# XiBank_V1_0.net
KiCad netlist of a schematic drawn in Altium Designer
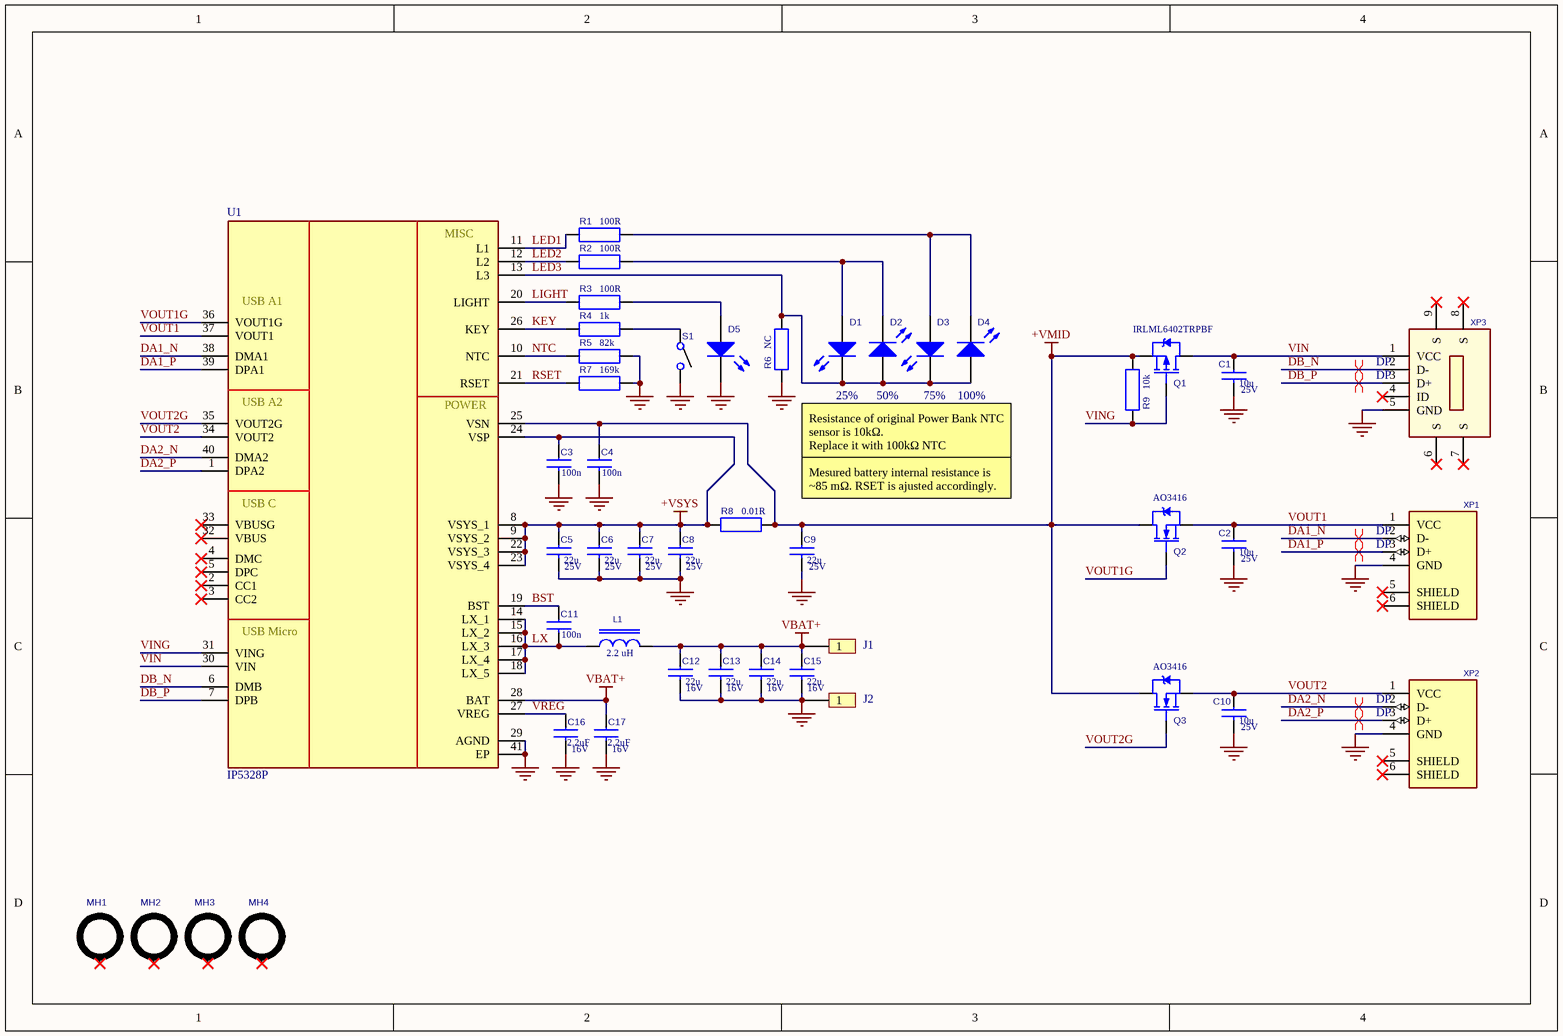
[diagram p0: XiBank_V1.0.SchDoc]

(export (version "E")
  (design (tool "Eeschema 10.0.6"))
  (components
    (comp (ref "C1")
      (value "10u")
      (footprint "CC0805")
      (description "10 µF ±10% 25V Ceramic Capacitor X5R 0805 (2012 Metric)")
      (fields
        (field (name "VOLTAGE") "25V")
        (field (name "TOLERANCE") "10%")
        (field (name "MANUFACTURER") "Samsung Electro-Mechanics")
      )
      (libsource (lib "Aldiva_Altium_Library") (part "Capacitor_nonpolar_case"))
    )
    (comp (ref "C2")
      (value "10u")
      (footprint "CC0805")
      (description "10 µF ±10% 25V Ceramic Capacitor X5R 0805 (2012 Metric)")
      (fields
        (field (name "VOLTAGE") "25V")
        (field (name "TOLERANCE") "10%")
        (field (name "MANUFACTURER") "Samsung Electro-Mechanics")
      )
      (libsource (lib "Aldiva_Altium_Library") (part "Capacitor_nonpolar_case"))
    )
    (comp (ref "C3")
      (value "100n")
      (footprint "CC0603")
      (description "0.1 µF ±10% 50V Ceramic Capacitor X7R 0603 (1608 Metric)")
      (fields (field (name "VOLTAGE") "50V") (field (name "TOLERANCE") "10%"))
      (libsource (lib "Aldiva_Altium_Library") (part "Capacitor_nonpolar_case"))
    )
    (comp (ref "C4")
      (value "100n")
      (footprint "CC0603")
      (description "0.1 µF ±10% 50V Ceramic Capacitor X7R 0603 (1608 Metric)")
      (fields (field (name "VOLTAGE") "50V") (field (name "TOLERANCE") "10%"))
      (libsource (lib "Aldiva_Altium_Library") (part "Capacitor_nonpolar_case"))
    )
    (comp (ref "C5")
      (value "22u")
      (footprint "CC0805")
      (description "22 µF ±20% 25V Ceramic Capacitor X5R 0805 (2012 Metric)")
      (fields
        (field (name "VOLTAGE") "25V")
        (field (name "TOLERANCE") "10%")
        (field (name "MANUFACTURER") "Samsung Electro-Mechanics")
      )
      (libsource (lib "Aldiva_Altium_Library") (part "Capacitor_nonpolar_case"))
    )
    (comp (ref "C6")
      (value "22u")
      (footprint "CC0805")
      (description "22 µF ±20% 25V Ceramic Capacitor X5R 0805 (2012 Metric)")
      (fields
        (field (name "VOLTAGE") "25V")
        (field (name "TOLERANCE") "10%")
        (field (name "MANUFACTURER") "Samsung Electro-Mechanics")
      )
      (libsource (lib "Aldiva_Altium_Library") (part "Capacitor_nonpolar_case"))
    )
    (comp (ref "C7")
      (value "22u")
      (footprint "CC0805")
      (description "22 µF ±20% 25V Ceramic Capacitor X5R 0805 (2012 Metric)")
      (fields
        (field (name "VOLTAGE") "25V")
        (field (name "TOLERANCE") "10%")
        (field (name "MANUFACTURER") "Samsung Electro-Mechanics")
      )
      (libsource (lib "Aldiva_Altium_Library") (part "Capacitor_nonpolar_case"))
    )
    (comp (ref "C8")
      (value "22u")
      (footprint "CC0805")
      (description "22 µF ±20% 25V Ceramic Capacitor X5R 0805 (2012 Metric)")
      (fields
        (field (name "VOLTAGE") "25V")
        (field (name "TOLERANCE") "10%")
        (field (name "MANUFACTURER") "Samsung Electro-Mechanics")
      )
      (libsource (lib "Aldiva_Altium_Library") (part "Capacitor_nonpolar_case"))
    )
    (comp (ref "C9")
      (value "22u")
      (footprint "CC0805")
      (description "22 µF ±20% 25V Ceramic Capacitor X5R 0805 (2012 Metric)")
      (fields
        (field (name "VOLTAGE") "25V")
        (field (name "TOLERANCE") "10%")
        (field (name "MANUFACTURER") "Samsung Electro-Mechanics")
      )
      (libsource (lib "Aldiva_Altium_Library") (part "Capacitor_nonpolar_case"))
    )
    (comp (ref "C10")
      (value "10u")
      (footprint "CC0805")
      (description "10 µF ±10% 25V Ceramic Capacitor X5R 0805 (2012 Metric)")
      (fields
        (field (name "VOLTAGE") "25V")
        (field (name "TOLERANCE") "10%")
        (field (name "MANUFACTURER") "Samsung Electro-Mechanics")
      )
      (libsource (lib "Aldiva_Altium_Library") (part "Capacitor_nonpolar_case"))
    )
    (comp (ref "C11")
      (value "100n")
      (footprint "CC0603")
      (description "0.1 µF ±10% 50V Ceramic Capacitor X7R 0603 (1608 Metric)")
      (fields (field (name "VOLTAGE") "50V") (field (name "TOLERANCE") "10%"))
      (libsource (lib "Aldiva_Altium_Library") (part "Capacitor_nonpolar_case"))
    )
    (comp (ref "C12")
      (value "22u")
      (footprint "CC0805")
      (description "22 µF ±20% 16V Ceramic Capacitor X5R 0805 (2012 Metric)")
      (fields
        (field (name "VOLTAGE") "16V")
        (field (name "TOLERANCE") "10%")
        (field (name "MANUFACTURER") "Samsung Electro-Mechanics")
      )
      (libsource (lib "Aldiva_Altium_Library") (part "Capacitor_nonpolar_case"))
    )
    (comp (ref "C13")
      (value "22u")
      (footprint "CC0805")
      (description "22 µF ±20% 16V Ceramic Capacitor X5R 0805 (2012 Metric)")
      (fields
        (field (name "VOLTAGE") "16V")
        (field (name "TOLERANCE") "10%")
        (field (name "MANUFACTURER") "Samsung Electro-Mechanics")
      )
      (libsource (lib "Aldiva_Altium_Library") (part "Capacitor_nonpolar_case"))
    )
    (comp (ref "C14")
      (value "22u")
      (footprint "CC0805")
      (description "22 µF ±20% 16V Ceramic Capacitor X5R 0805 (2012 Metric)")
      (fields
        (field (name "VOLTAGE") "16V")
        (field (name "TOLERANCE") "10%")
        (field (name "MANUFACTURER") "Samsung Electro-Mechanics")
      )
      (libsource (lib "Aldiva_Altium_Library") (part "Capacitor_nonpolar_case"))
    )
    (comp (ref "C15")
      (value "22u")
      (footprint "CC0805")
      (description "22 µF ±20% 16V Ceramic Capacitor X5R 0805 (2012 Metric)")
      (fields
        (field (name "VOLTAGE") "16V")
        (field (name "TOLERANCE") "10%")
        (field (name "MANUFACTURER") "Samsung Electro-Mechanics")
      )
      (libsource (lib "Aldiva_Altium_Library") (part "Capacitor_nonpolar_case"))
    )
    (comp (ref "C16")
      (value "2.2uF")
      (footprint "CC0603")
      (description "2.2 µF ±10% 16V Ceramic Capacitor X5R 0603 (1608 Metric)")
      (fields
        (field (name "VOLTAGE") "16V")
        (field (name "TOLERANCE") "10%")
        (field (name "MANUFACTURER") "Samsung Electro-Mechanics")
      )
      (libsource (lib "Aldiva_Altium_Library") (part "Capacitor_nonpolar_case"))
    )
    (comp (ref "C17")
      (value "2.2uF")
      (footprint "CC0603")
      (description "2.2 µF ±10% 16V Ceramic Capacitor X5R 0603 (1608 Metric)")
      (fields
        (field (name "VOLTAGE") "16V")
        (field (name "TOLERANCE") "10%")
        (field (name "MANUFACTURER") "Samsung Electro-Mechanics")
      )
      (libsource (lib "Miscellaneous Connectors") (part "Capacitor_nonpolar_case"))
    )
    (comp (ref "D1")
      (value "LTW-C191DS5")
      (footprint "LED0603")
      (description "White LED Indication - Discrete 2.93V 0603 (1608 Metric)")
      (fields (field (name "VOLTAGE") "2.93V") (field (name "MANUFACTURER") "Lite-On Inc."))
      (libsource (lib "Aldiva_Altium_Library") (part "LED"))
    )
    (comp (ref "D2")
      (value "LTW-C191DS5")
      (footprint "LED0603")
      (description "White LED Indication - Discrete 2.93V 0603 (1608 Metric)")
      (fields (field (name "VOLTAGE") "2.93V") (field (name "MANUFACTURER") "Lite-On Inc."))
      (libsource (lib "Aldiva_Altium_Library") (part "LED"))
    )
    (comp (ref "D3")
      (value "LTW-C191DS5")
      (footprint "LED0603")
      (description "White LED Indication - Discrete 2.93V 0603 (1608 Metric)")
      (fields (field (name "VOLTAGE") "2.93V") (field (name "MANUFACTURER") "Lite-On Inc."))
      (libsource (lib "Aldiva_Altium_Library") (part "LED"))
    )
    (comp (ref "D4")
      (value "LTW-C191DS5")
      (footprint "LED0603")
      (description "White LED Indication - Discrete 2.93V 0603 (1608 Metric)")
      (fields (field (name "VOLTAGE") "2.93V") (field (name "MANUFACTURER") "Lite-On Inc."))
      (libsource (lib "Aldiva_Altium_Library") (part "LED"))
    )
    (comp (ref "D5")
      (value "LTW-C191DS5")
      (footprint "LED0603")
      (description "White LED Indication - Discrete 2.93V 0603 (1608 Metric)")
      (fields (field (name "VOLTAGE") "2.93V") (field (name "MANUFACTURER") "Lite-On Inc."))
      (libsource (lib "Aldiva_Altium_Library") (part "LED"))
    )
    (comp (ref "J1")
      (value "Header 1pin")
      (footprint "1 Hole")
      (description "THRU header 1pins, MALE, Vertical, 2.54mm pitch")
      (fields
        (field (name "PART NUMBER") "HEADER_2.54_THR_1x1P_MV")
        (field (name "MANUFACTURER PART NUMBER") "TSW-101-07-L-S")
        (field (name "PUBLISHER") "dlitvinenko")
      )
      (libsource (lib "Aldiva_Altium_Library") (part "Header 1pin"))
    )
    (comp (ref "J2")
      (value "Header 1pin")
      (footprint "1 Hole")
      (description "THRU header 1pins, MALE, Vertical, 2.54mm pitch")
      (fields
        (field (name "PART NUMBER") "HEADER_2.54_THR_1x1P_MV")
        (field (name "MANUFACTURER PART NUMBER") "TSW-101-07-L-S")
        (field (name "PUBLISHER") "dlitvinenko")
      )
      (libsource (lib "Aldiva_Altium_Library") (part "Header 1pin"))
    )
    (comp (ref "L1")
      (value "2.2 uH")
      (footprint "HPI1040100")
      (description "SMD Power Inductor, 2.2uH, 12A, 6.5mΩ")
      (fields
        (field (name "PART NUMBER") "HPI1040-2R2")
        (field (name "TOLERANCE") "20%")
        (field (name "PUBLISHER") "dlegkobyt")
      )
      (libsource (lib "SamacSys") (part "INDUCTOR"))
    )
    (comp (ref "MH1")
      (value "MH_3.5_NONPLATED")
      (footprint "MH_3.5_NONPLATED")
      (description "Mounting hole misc, non plated")
      (libsource (lib "Aldiva_Altium_Library") (part "MH_MISC"))
    )
    (comp (ref "MH2")
      (value "MH_3.5_NONPLATED")
      (footprint "MH_3.5_NONPLATED")
      (description "Mounting hole misc, non plated")
      (libsource (lib "Aldiva_Altium_Library") (part "MH_MISC"))
    )
    (comp (ref "MH3")
      (value "MH_3.5_NONPLATED")
      (footprint "MH_3.5_NONPLATED")
      (description "Mounting hole misc, non plated")
      (libsource (lib "Aldiva_Altium_Library") (part "MH_MISC"))
    )
    (comp (ref "MH4")
      (value "MH_3.5_NONPLATED")
      (footprint "MH_3.5_NONPLATED")
      (description "Mounting hole misc, non plated")
      (libsource (lib "Aldiva_Altium_Library") (part "MH_MISC"))
    )
    (comp (ref "Q1")
      (value "IRLML6402TRPBF")
      (footprint "SOT23-3")
      (description "P-Channel 20 V 3.7A (Ta) 1.3W (Ta) Surface Mount Micro3™/SOT-23")
      (fields
        (field (name "MANUFACTURER") "Infineon Technologies")
        (field (name "MANUFACTURER PART NUMBER") "IRLML6402TRPBF")
      )
      (libsource (lib "Aldiva_Altium_Library") (part "P-channel_transistor_SOT23-3"))
    )
    (comp (ref "Q2")
      (value "AO3416")
      (footprint "SOT23-3")
      (description "N-Channel 20 V 6.5A (Ta) 1.4W (Ta) Surface Mount SOT-23-3")
      (fields
        (field (name "MANUFACTURER") "Alpha & Omega Semiconductor Inc.")
        (field (name "MANUFACTURER PART NUMBER") "AO3416")
      )
      (libsource (lib "Aldiva_Altium_Library") (part "N-channel_transistor_SOT23-3"))
    )
    (comp (ref "Q3")
      (value "AO3416")
      (footprint "SOT23-3")
      (description "N-Channel 20 V 6.5A (Ta) 1.4W (Ta) Surface Mount SOT-23-3")
      (fields
        (field (name "MANUFACTURER") "Alpha & Omega Semiconductor Inc.")
        (field (name "MANUFACTURER PART NUMBER") "AO3416")
      )
      (libsource (lib "Aldiva_Altium_Library") (part "N-channel_transistor_SOT23-3"))
    )
    (comp (ref "R1")
      (value "100R")
      (footprint "RC0603")
      (description "100 ±1% 0.1W, 1/10W Chip Resistor 0603 (1608 Metric) Moisture Resistant Thick Film")
      (fields (field (name "VOLTAGE") "50V") (field (name "POWER") "1/10W"))
      (libsource (lib "Aldiva_Altium_Library") (part "Resistor"))
    )
    (comp (ref "R2")
      (value "100R")
      (footprint "RC0603")
      (description "100 ±1% 0.1W, 1/10W Chip Resistor 0603 (1608 Metric) Moisture Resistant Thick Film")
      (fields (field (name "VOLTAGE") "50V") (field (name "POWER") "1/10W"))
      (libsource (lib "Aldiva_Altium_Library") (part "Resistor"))
    )
    (comp (ref "R3")
      (value "100R")
      (footprint "RC0603")
      (description "100 ±1% 0.1W, 1/10W Chip Resistor 0603 (1608 Metric) Moisture Resistant Thick Film")
      (fields (field (name "VOLTAGE") "50V") (field (name "POWER") "1/10W"))
      (libsource (lib "Aldiva_Altium_Library") (part "Resistor"))
    )
    (comp (ref "R4")
      (value "1k")
      (footprint "RC0603")
      (description "1k ±1% 0.1W, 1/10W Chip Resistor 0603 (1608 Metric) Moisture Resistant Thick Film")
      (fields (field (name "VOLTAGE") "50V") (field (name "POWER") "1/10W"))
      (libsource (lib "Aldiva_Altium_Library") (part "Resistor"))
    )
    (comp (ref "R5")
      (value "82k")
      (footprint "RC0603")
      (description "82 kOhms ±1% 0.1W, 1/10W Chip Resistor 0603 (1608 Metric) Moisture Resistant Thick Film")
      (fields (field (name "VOLTAGE") "50V") (field (name "POWER") "1/10W"))
      (libsource (lib "Aldiva_Altium_Library") (part "Resistor"))
    )
    (comp (ref "R6")
      (value "NC")
      (footprint "RC0603")
      (description "200k ±1% 0.1W, 1/10W Chip Resistor 0603 (1608 Metric) Moisture Resistant Thick Film")
      (fields (field (name "VOLTAGE") "50V") (field (name "POWER") "1/10W"))
      (libsource (lib "Aldiva_Altium_Library") (part "Resistor"))
    )
    (comp (ref "R7")
      (value "169k")
      (footprint "RC0603")
      (description "169k ±1% 0.1W, 1/10W Chip Resistor 0603 (1608 Metric) Moisture Resistant Thick Film")
      (fields (field (name "VOLTAGE") "50V") (field (name "POWER") "1/10W"))
      (libsource (lib "Aldiva_Altium_Library") (part "Resistor"))
    )
    (comp (ref "R8")
      (value "0.01R")
      (footprint "RC1206")
      (fields (field (name "VOLTAGE") "200V") (field (name "POWER") "1/4W") (field (name "TOLERANCE") "1%"))
      (libsource (lib "Aldiva_Altium_Library") (part "Resistor"))
    )
    (comp (ref "R9")
      (value "10k")
      (footprint "RC0603")
      (description "10k ±1% 0.1W, 1/10W Chip Resistor 0603 (1608 Metric) Moisture Resistant Thick Film")
      (fields (field (name "VOLTAGE") "50V") (field (name "POWER") "1/10W"))
      (libsource (lib "Aldiva_Altium_Library") (part "Resistor"))
    )
    (comp (ref "S1")
      (value "~")
      (footprint "SW_LS10N2T_CIT")
      (description "Tactile Switch SPST-NO Side Actuated Surface Mount, Right Angle")
      (fields
        (field (name "MANUFACTURER") "Citizen")
        (field (name "MANUFACTURER PART NUMBER") "LS10N2T")
        (field (name "COPYRIGHT") "Copyright (C) 2022 Ultra Librarian. All rights reserved.")
      )
      (libsource (lib "AltiumV15") (part "LS10N2T"))
    )
    (comp (ref "U1")
      (value "IP5328P")
      (footprint "SamacSys:QFN50P600X600X80-41N")
      (fields (field (name "MANUFACTURER") "INJOINIC Technology"))
      (libsource (lib "MI_PowerBank") (part "IP5328P"))
    )
    (comp (ref "XP1")
      (value "USB-A Conn")
      (footprint "0480372200")
      (description "USB-A (USB TYPE-A) USB 2.0 Plug Connector 4 Position Surface Mount, Right Angle")
      (fields (field (name "MANUFACTURER") "NULL"))
      (libsource (lib "Aldiva_Altium_Library") (part "USB-A Conn"))
    )
    (comp (ref "XP2")
      (value "USB-A Conn")
      (footprint "0480372200")
      (description "USB-A (USB TYPE-A) USB 2.0 Plug Connector 4 Position Surface Mount, Right Angle")
      (fields (field (name "MANUFACTURER") "NULL"))
      (libsource (lib "Aldiva_Altium_Library") (part "USB-A Conn"))
    )
    (comp (ref "XP3")
      (value "ZX80-B-5P")
      (footprint "10118194-0001LF")
      (description "Micro USB B Right Angled  Socket, SMD")
      (fields (field (name "MANUFACTURER") "FCI") (field (name "MANUFACTURER PART NUMBER") "10118194-0001LF"))
      (libsource (lib "Aldiva_Altium_Library") (part "ZX80-B-5P"))
    )
  )
  (nets
    (net (code "1") (name "+VMID") (class "Default")
      (node (ref "C4") (pin "1") (pinfunction "1_1") (pintype "passive"))
      (node (ref "C9") (pin "1") (pinfunction "1_1") (pintype "passive"))
      (node (ref "Q1") (pin "2") (pinfunction "S_2") (pintype "passive"))
      (node (ref "Q2") (pin "3") (pinfunction "D_3") (pintype "passive"))
      (node (ref "Q3") (pin "3") (pinfunction "D_3") (pintype "passive"))
      (node (ref "R8") (pin "2") (pinfunction "2_2") (pintype "passive"))
      (node (ref "R9") (pin "2") (pinfunction "2_2") (pintype "passive"))
      (node (ref "U1") (pin "25") (pinfunction "VSN_25") (pintype "passive"))
    )
    (net (code "2") (name "+VSYS") (class "Default")
      (node (ref "C3") (pin "1") (pinfunction "1_1") (pintype "passive"))
      (node (ref "C5") (pin "1") (pinfunction "1_1") (pintype "passive"))
      (node (ref "C6") (pin "1") (pinfunction "1_1") (pintype "passive"))
      (node (ref "C7") (pin "1") (pinfunction "1_1") (pintype "passive"))
      (node (ref "C8") (pin "1") (pinfunction "1_1") (pintype "passive"))
      (node (ref "R8") (pin "1") (pinfunction "1_1") (pintype "passive"))
      (node (ref "U1") (pin "22") (pinfunction "VSYS_3_22") (pintype "passive"))
      (node (ref "U1") (pin "23") (pinfunction "VSYS_4_23") (pintype "passive"))
      (node (ref "U1") (pin "24") (pinfunction "VSP_24") (pintype "passive"))
      (node (ref "U1") (pin "8") (pinfunction "VSYS_1_8") (pintype "passive"))
      (node (ref "U1") (pin "9") (pinfunction "VSYS_2_9") (pintype "passive"))
    )
    (net (code "3") (name "/BST") (class "Default")
      (node (ref "C11") (pin "1") (pinfunction "1_1") (pintype "passive"))
      (node (ref "U1") (pin "19") (pinfunction "BST_19") (pintype "passive"))
    )
    (net (code "4") (name "/DA1_N") (class "Default")
      (node (ref "U1") (pin "38") (pinfunction "DMA1_38") (pintype "passive"))
      (node (ref "XP1") (pin "2") (pinfunction "D-_2") (pintype "bidirectional"))
    )
    (net (code "5") (name "/DA1_P") (class "Default")
      (node (ref "U1") (pin "39") (pinfunction "DPA1_39") (pintype "passive"))
      (node (ref "XP1") (pin "3") (pinfunction "D+_3") (pintype "bidirectional"))
    )
    (net (code "6") (name "/DA2_N") (class "Default")
      (node (ref "U1") (pin "40") (pinfunction "DMA2_40") (pintype "passive"))
      (node (ref "XP2") (pin "2") (pinfunction "D-_2") (pintype "bidirectional"))
    )
    (net (code "7") (name "/DA2_P") (class "Default")
      (node (ref "U1") (pin "1") (pinfunction "DPA2_1") (pintype "passive"))
      (node (ref "XP2") (pin "3") (pinfunction "D+_3") (pintype "bidirectional"))
    )
    (net (code "8") (name "/DB_N") (class "Default")
      (node (ref "U1") (pin "6") (pinfunction "DMB_6") (pintype "passive"))
      (node (ref "XP3") (pin "2") (pinfunction "D-_2") (pintype "passive"))
    )
    (net (code "9") (name "/DB_P") (class "Default")
      (node (ref "U1") (pin "7") (pinfunction "DPB_7") (pintype "passive"))
      (node (ref "XP3") (pin "3") (pinfunction "D+_3") (pintype "passive"))
    )
    (net (code "10") (name "/KEY") (class "Default")
      (node (ref "R4") (pin "1") (pinfunction "1_1") (pintype "passive"))
      (node (ref "U1") (pin "26") (pinfunction "KEY_26") (pintype "passive"))
    )
    (net (code "11") (name "/LED1") (class "Default")
      (node (ref "R1") (pin "1") (pinfunction "1_1") (pintype "passive"))
      (node (ref "U1") (pin "11") (pinfunction "L1_11") (pintype "passive"))
    )
    (net (code "12") (name "/LED2") (class "Default")
      (node (ref "R2") (pin "1") (pinfunction "1_1") (pintype "passive"))
      (node (ref "U1") (pin "12") (pinfunction "L2_12") (pintype "passive"))
    )
    (net (code "13") (name "/LED3") (class "Default")
      (node (ref "D1") (pin "1") (pinfunction "K_1") (pintype "passive"))
      (node (ref "D2") (pin "2") (pinfunction "A_2") (pintype "passive"))
      (node (ref "D3") (pin "1") (pinfunction "K_1") (pintype "passive"))
      (node (ref "D4") (pin "2") (pinfunction "A_2") (pintype "passive"))
      (node (ref "R6") (pin "2") (pinfunction "2_2") (pintype "passive"))
      (node (ref "U1") (pin "13") (pinfunction "L3_13") (pintype "passive"))
    )
    (net (code "14") (name "/LIGHT") (class "Default")
      (node (ref "R3") (pin "1") (pinfunction "1_1") (pintype "passive"))
      (node (ref "U1") (pin "20") (pinfunction "LIGHT_20") (pintype "passive"))
    )
    (net (code "15") (name "/LX") (class "Default")
      (node (ref "C11") (pin "2") (pinfunction "2_2") (pintype "passive"))
      (node (ref "L1") (pin "1") (pinfunction "1_1") (pintype "passive"))
      (node (ref "U1") (pin "14") (pinfunction "LX_1_14") (pintype "passive"))
      (node (ref "U1") (pin "15") (pinfunction "LX_2_15") (pintype "passive"))
      (node (ref "U1") (pin "16") (pinfunction "LX_3_16") (pintype "passive"))
      (node (ref "U1") (pin "17") (pinfunction "LX_4_17") (pintype "passive"))
      (node (ref "U1") (pin "18") (pinfunction "LX_5_18") (pintype "passive"))
    )
    (net (code "16") (name "/NTC") (class "Default")
      (node (ref "R5") (pin "1") (pinfunction "1_1") (pintype "passive"))
      (node (ref "U1") (pin "10") (pinfunction "NTC_10") (pintype "passive"))
    )
    (net (code "17") (name "/RSET") (class "Default")
      (node (ref "R7") (pin "1") (pinfunction "1_1") (pintype "passive"))
      (node (ref "U1") (pin "21") (pinfunction "RSET_21") (pintype "passive"))
    )
    (net (code "18") (name "/VIN") (class "Default")
      (node (ref "C1") (pin "1") (pinfunction "1_1") (pintype "passive"))
      (node (ref "Q1") (pin "3") (pinfunction "D_3") (pintype "passive"))
      (node (ref "U1") (pin "30") (pinfunction "VIN_30") (pintype "passive"))
      (node (ref "XP3") (pin "1") (pinfunction "VCC_1") (pintype "passive"))
    )
    (net (code "19") (name "/VING") (class "Default")
      (node (ref "Q1") (pin "1") (pinfunction "G_1") (pintype "passive"))
      (node (ref "R9") (pin "1") (pinfunction "1_1") (pintype "passive"))
      (node (ref "U1") (pin "31") (pinfunction "VING_31") (pintype "passive"))
    )
    (net (code "20") (name "/VOUT1") (class "Default")
      (node (ref "C2") (pin "1") (pinfunction "1_1") (pintype "passive"))
      (node (ref "Q2") (pin "2") (pinfunction "S_2") (pintype "passive"))
      (node (ref "U1") (pin "37") (pinfunction "VOUT1_37") (pintype "passive"))
      (node (ref "XP1") (pin "1") (pinfunction "VCC_1") (pintype "power_in"))
    )
    (net (code "21") (name "/VOUT1G") (class "Default")
      (node (ref "Q2") (pin "1") (pinfunction "G_1") (pintype "passive"))
      (node (ref "U1") (pin "36") (pinfunction "VOUT1G_36") (pintype "passive"))
    )
    (net (code "22") (name "/VOUT2") (class "Default")
      (node (ref "C10") (pin "1") (pinfunction "1_1") (pintype "passive"))
      (node (ref "Q3") (pin "2") (pinfunction "S_2") (pintype "passive"))
      (node (ref "U1") (pin "34") (pinfunction "VOUT2_34") (pintype "passive"))
      (node (ref "XP2") (pin "1") (pinfunction "VCC_1") (pintype "power_in"))
    )
    (net (code "23") (name "/VOUT2G") (class "Default")
      (node (ref "Q3") (pin "1") (pinfunction "G_1") (pintype "passive"))
      (node (ref "U1") (pin "35") (pinfunction "VOUT2G_35") (pintype "passive"))
    )
    (net (code "24") (name "/VREG") (class "Default")
      (node (ref "C16") (pin "1") (pinfunction "1_1") (pintype "passive"))
      (node (ref "U1") (pin "27") (pinfunction "VREG_27") (pintype "passive"))
    )
    (net (code "25") (name "GND") (class "Default")
      (node (ref "C1") (pin "2") (pinfunction "2_2") (pintype "passive"))
      (node (ref "C10") (pin "2") (pinfunction "2_2") (pintype "passive"))
      (node (ref "C12") (pin "2") (pinfunction "2_2") (pintype "passive"))
      (node (ref "C13") (pin "2") (pinfunction "2_2") (pintype "passive"))
      (node (ref "C14") (pin "2") (pinfunction "2_2") (pintype "passive"))
      (node (ref "C15") (pin "2") (pinfunction "2_2") (pintype "passive"))
      (node (ref "C16") (pin "2") (pinfunction "2_2") (pintype "passive"))
      (node (ref "C17") (pin "2") (pinfunction "2_2") (pintype "passive"))
      (node (ref "C2") (pin "2") (pinfunction "2_2") (pintype "passive"))
      (node (ref "C3") (pin "2") (pinfunction "2_2") (pintype "passive"))
      (node (ref "C4") (pin "2") (pinfunction "2_2") (pintype "passive"))
      (node (ref "C5") (pin "2") (pinfunction "2_2") (pintype "passive"))
      (node (ref "C6") (pin "2") (pinfunction "2_2") (pintype "passive"))
      (node (ref "C7") (pin "2") (pinfunction "2_2") (pintype "passive"))
      (node (ref "C8") (pin "2") (pinfunction "2_2") (pintype "passive"))
      (node (ref "C9") (pin "2") (pinfunction "2_2") (pintype "passive"))
      (node (ref "D5") (pin "1") (pinfunction "K_1") (pintype "passive"))
      (node (ref "J2") (pin "1") (pinfunction "1_1") (pintype "passive"))
      (node (ref "R5") (pin "2") (pinfunction "2_2") (pintype "passive"))
      (node (ref "R6") (pin "1") (pinfunction "1_1") (pintype "passive"))
      (node (ref "R7") (pin "2") (pinfunction "2_2") (pintype "passive"))
      (node (ref "S1") (pin "2") (pinfunction "2_2") (pintype "passive"))
      (node (ref "U1") (pin "29") (pinfunction "AGND_29") (pintype "passive"))
      (node (ref "U1") (pin "41") (pinfunction "EP_41") (pintype "passive"))
      (node (ref "XP1") (pin "4") (pinfunction "GND_4") (pintype "power_in"))
      (node (ref "XP2") (pin "4") (pinfunction "GND_4") (pintype "power_in"))
      (node (ref "XP3") (pin "5") (pinfunction "GND_5") (pintype "passive"))
    )
    (net (code "26") (name "Net-(D1-A)") (class "Default")
      (node (ref "D1") (pin "2") (pinfunction "A_2") (pintype "passive"))
      (node (ref "D2") (pin "1") (pinfunction "K_1") (pintype "passive"))
      (node (ref "R2") (pin "2") (pinfunction "2_2") (pintype "passive"))
    )
    (net (code "27") (name "Net-(D3-A)") (class "Default")
      (node (ref "D3") (pin "2") (pinfunction "A_2") (pintype "passive"))
      (node (ref "D4") (pin "1") (pinfunction "K_1") (pintype "passive"))
      (node (ref "R1") (pin "2") (pinfunction "2_2") (pintype "passive"))
    )
    (net (code "28") (name "Net-(D5-A)") (class "Default")
      (node (ref "D5") (pin "2") (pinfunction "A_2") (pintype "passive"))
      (node (ref "R3") (pin "2") (pinfunction "2_2") (pintype "passive"))
    )
    (net (code "29") (name "Net-(R4-Pad2)") (class "Default")
      (node (ref "R4") (pin "2") (pinfunction "2_2") (pintype "passive"))
      (node (ref "S1") (pin "1") (pinfunction "1_1") (pintype "passive"))
    )
    (net (code "30") (name "VBAT+") (class "Default")
      (node (ref "C12") (pin "1") (pinfunction "1_1") (pintype "passive"))
      (node (ref "C13") (pin "1") (pinfunction "1_1") (pintype "passive"))
      (node (ref "C14") (pin "1") (pinfunction "1_1") (pintype "passive"))
      (node (ref "C15") (pin "1") (pinfunction "1_1") (pintype "passive"))
      (node (ref "C17") (pin "1") (pinfunction "1_1") (pintype "passive"))
      (node (ref "J1") (pin "1") (pinfunction "1_1") (pintype "passive"))
      (node (ref "L1") (pin "2") (pinfunction "2_2") (pintype "passive"))
      (node (ref "U1") (pin "28") (pinfunction "BAT_28") (pintype "passive"))
    )
    (net (code "31") (name "unconnected-(MH1-Pad0)") (class "Default")
      (node (ref "MH1") (pin "0") (pinfunction "0_0") (pintype "passive+no_connect"))
    )
    (net (code "32") (name "unconnected-(MH2-Pad0)") (class "Default")
      (node (ref "MH2") (pin "0") (pinfunction "0_0") (pintype "passive+no_connect"))
    )
    (net (code "33") (name "unconnected-(MH3-Pad0)") (class "Default")
      (node (ref "MH3") (pin "0") (pinfunction "0_0") (pintype "passive+no_connect"))
    )
    (net (code "34") (name "unconnected-(MH4-Pad0)") (class "Default")
      (node (ref "MH4") (pin "0") (pinfunction "0_0") (pintype "passive+no_connect"))
    )
    (net (code "35") (name "unconnected-(U1-CC1-Pad2)") (class "Default")
      (node (ref "U1") (pin "2") (pinfunction "CC1_2") (pintype "passive+no_connect"))
    )
    (net (code "36") (name "unconnected-(U1-CC2-Pad3)") (class "Default")
      (node (ref "U1") (pin "3") (pinfunction "CC2_3") (pintype "passive+no_connect"))
    )
    (net (code "37") (name "unconnected-(U1-DMC-Pad4)") (class "Default")
      (node (ref "U1") (pin "4") (pinfunction "DMC_4") (pintype "passive+no_connect"))
    )
    (net (code "38") (name "unconnected-(U1-DPC-Pad5)") (class "Default")
      (node (ref "U1") (pin "5") (pinfunction "DPC_5") (pintype "passive+no_connect"))
    )
    (net (code "39") (name "unconnected-(U1-VBUS-Pad32)") (class "Default")
      (node (ref "U1") (pin "32") (pinfunction "VBUS_32") (pintype "passive+no_connect"))
    )
    (net (code "40") (name "unconnected-(U1-VBUSG-Pad33)") (class "Default")
      (node (ref "U1") (pin "33") (pinfunction "VBUSG_33") (pintype "passive+no_connect"))
    )
    (net (code "41") (name "unconnected-(XP1-SHIELD-Pad5)") (class "Default")
      (node (ref "XP1") (pin "5") (pinfunction "SHIELD_5") (pintype "passive+no_connect"))
    )
    (net (code "42") (name "unconnected-(XP1-SHIELD-Pad6)") (class "Default")
      (node (ref "XP1") (pin "6") (pinfunction "SHIELD_6") (pintype "passive+no_connect"))
    )
    (net (code "43") (name "unconnected-(XP2-SHIELD-Pad5)") (class "Default")
      (node (ref "XP2") (pin "5") (pinfunction "SHIELD_5") (pintype "passive+no_connect"))
    )
    (net (code "44") (name "unconnected-(XP2-SHIELD-Pad6)") (class "Default")
      (node (ref "XP2") (pin "6") (pinfunction "SHIELD_6") (pintype "passive+no_connect"))
    )
    (net (code "45") (name "unconnected-(XP3-ID-Pad4)") (class "Default")
      (node (ref "XP3") (pin "4") (pinfunction "ID_4") (pintype "passive+no_connect"))
    )
    (net (code "46") (name "unconnected-(XP3-S-Pad6)") (class "Default")
      (node (ref "XP3") (pin "6") (pinfunction "S_6") (pintype "passive+no_connect"))
    )
    (net (code "47") (name "unconnected-(XP3-S-Pad7)") (class "Default")
      (node (ref "XP3") (pin "7") (pinfunction "S_7") (pintype "passive+no_connect"))
    )
    (net (code "48") (name "unconnected-(XP3-S-Pad8)") (class "Default")
      (node (ref "XP3") (pin "8") (pinfunction "S_8") (pintype "passive+no_connect"))
    )
    (net (code "49") (name "unconnected-(XP3-S-Pad9)") (class "Default")
      (node (ref "XP3") (pin "9") (pinfunction "S_9") (pintype "passive+no_connect"))
    )
  )
)
